# Attiny_MCU_Module.net
KiCad netlist of a schematic drawn in EAGLE
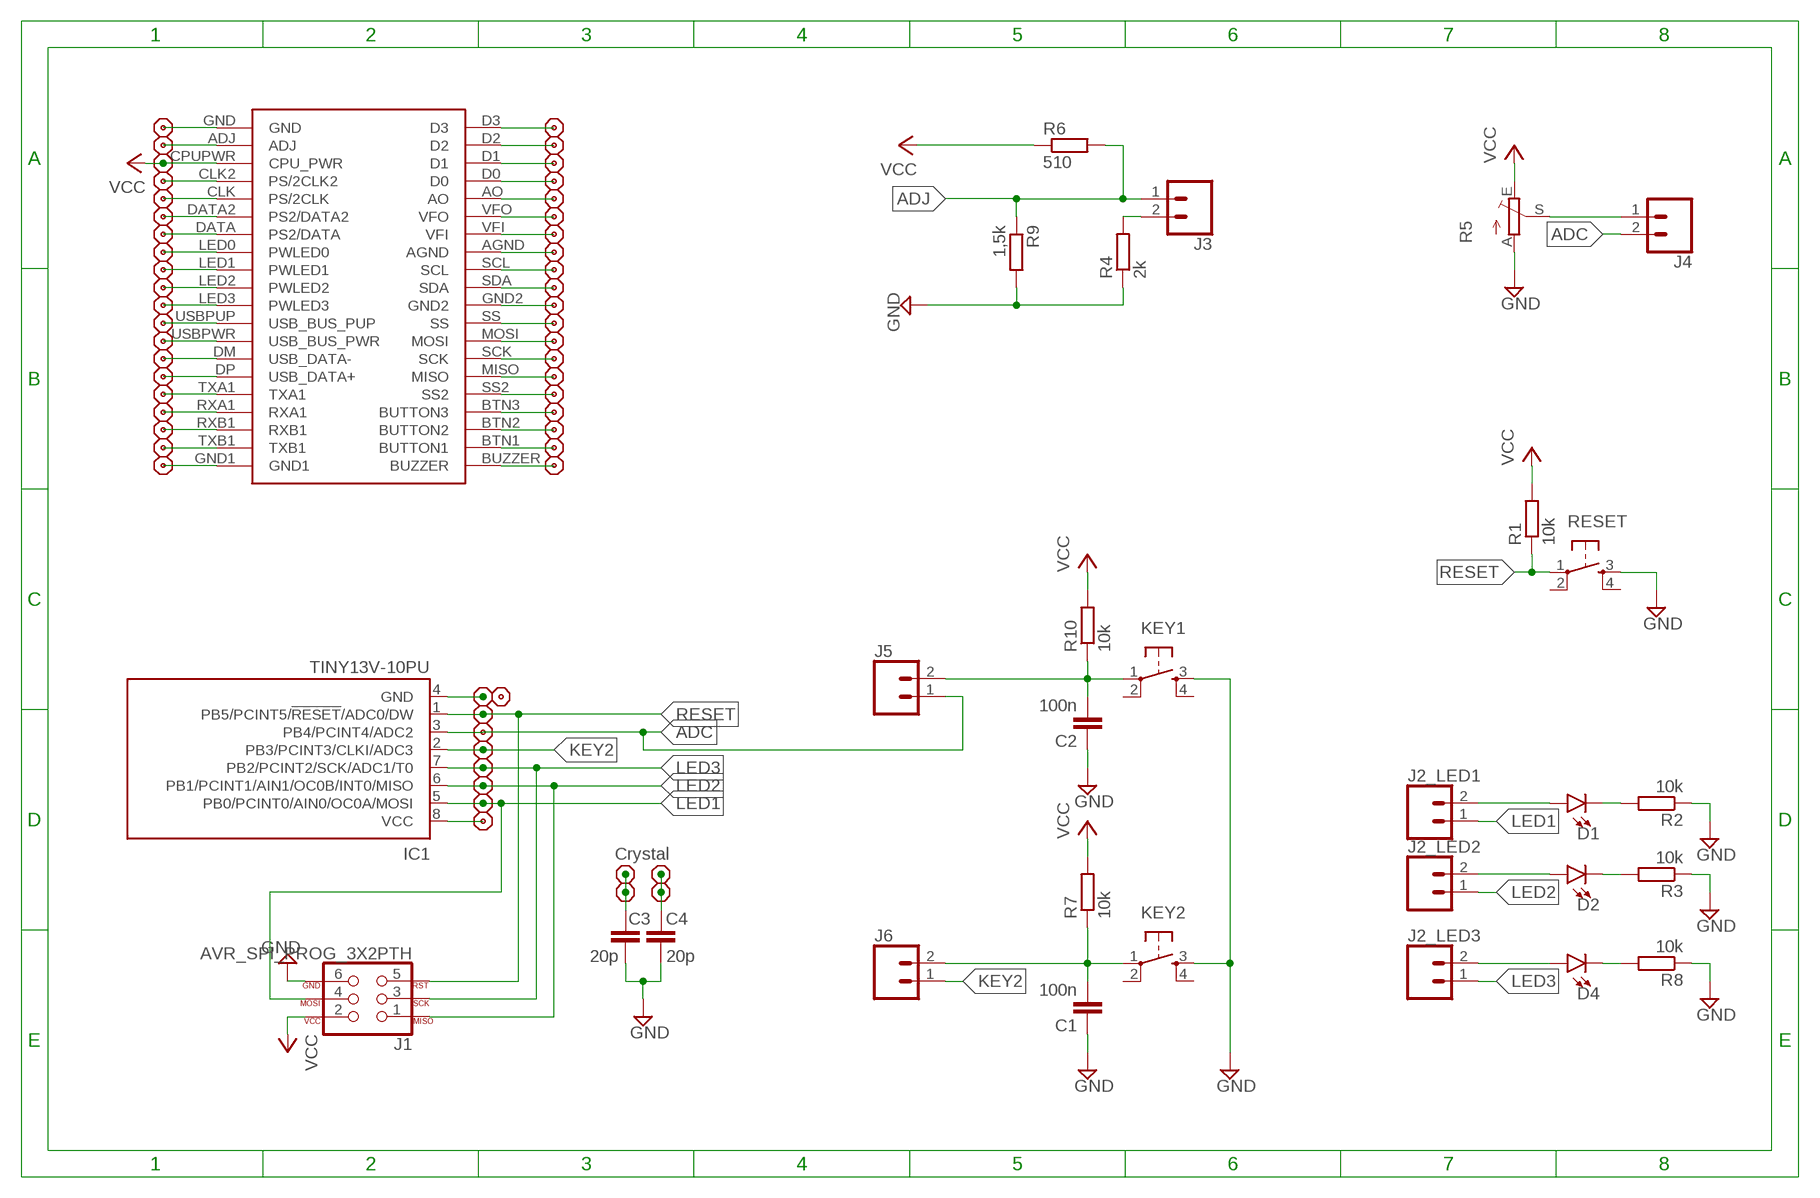
[diagram p0: schematic, sheet 1]

(export (version "E")
  (design (tool "Eeschema 10.0.6"))
  (components
    (comp (ref "C1")
      (value "100n")
      (footprint "eagle-import:C1206")
      (libsource (lib "eagle-import") (part "C-EUC1206"))
    )
    (comp (ref "C2")
      (value "100n")
      (footprint "eagle-import:C1206")
      (libsource (lib "eagle-import") (part "C-EUC1206"))
    )
    (comp (ref "C3")
      (value "20p")
      (footprint "eagle-import:C1206")
      (libsource (lib "eagle-import") (part "C-EUC1206"))
    )
    (comp (ref "C4")
      (value "20p")
      (footprint "eagle-import:C1206")
      (libsource (lib "eagle-import") (part "C-EUC1206"))
    )
    (comp (ref "D1")
      (value "LED1206")
      (footprint "eagle-import:LED-1206")
      (libsource (lib "eagle-import") (part "LED1206"))
    )
    (comp (ref "D2")
      (value "LED1206")
      (footprint "eagle-import:LED-1206")
      (libsource (lib "eagle-import") (part "LED1206"))
    )
    (comp (ref "D4")
      (value "LED1206")
      (footprint "eagle-import:LED-1206")
      (libsource (lib "eagle-import") (part "LED1206"))
    )
    (comp (ref "IC1")
      (value "TINY13V-10PU")
      (footprint "eagle-import:DIL08")
      (fields (field (name "MPN") "ATTINY13V-10PU"))
      (libsource (lib "eagle-import") (part "TINY13PUV-10"))
    )
    (comp (ref "J1")
      (value "AVR_SPI_PROG_3X2PTH")
      (footprint "eagle-import:2X3")
      (libsource (lib "eagle-import") (part "AVR_SPI_PROG_3X2PTH"))
    )
    (comp (ref "J2_LED1")
      (value "CONN_02")
      (footprint "eagle-import:1X02")
      (libsource (lib "eagle-import") (part "CONN_02"))
    )
    (comp (ref "J2_LED2")
      (value "CONN_02")
      (footprint "eagle-import:1X02")
      (libsource (lib "eagle-import") (part "CONN_02"))
    )
    (comp (ref "J2_LED3")
      (value "CONN_02")
      (footprint "eagle-import:1X02")
      (libsource (lib "eagle-import") (part "CONN_02"))
    )
    (comp (ref "J3")
      (value "CONN_02")
      (footprint "eagle-import:1X02")
      (libsource (lib "eagle-import") (part "CONN_02"))
    )
    (comp (ref "J4")
      (value "CONN_02")
      (footprint "eagle-import:1X02")
      (libsource (lib "eagle-import") (part "CONN_02"))
    )
    (comp (ref "J5")
      (value "CONN_02")
      (footprint "eagle-import:1X02")
      (libsource (lib "eagle-import") (part "CONN_02"))
    )
    (comp (ref "J6")
      (value "CONN_02")
      (footprint "eagle-import:1X02")
      (libsource (lib "eagle-import") (part "CONN_02"))
    )
    (comp (ref "JP1")
      (value "PINHD-1X1PIN")
      (footprint "eagle-import:1X01")
      (libsource (lib "eagle-import") (part "PINHD-1X1PIN"))
    )
    (comp (ref "JP2")
      (value "PINHD-1X1PIN")
      (footprint "eagle-import:1X01")
      (libsource (lib "eagle-import") (part "PINHD-1X1PIN"))
    )
    (comp (ref "JP3")
      (value "PINHD-1X1PIN")
      (footprint "eagle-import:1X01")
      (libsource (lib "eagle-import") (part "PINHD-1X1PIN"))
    )
    (comp (ref "JP4")
      (value "PINHD-1X1PIN")
      (footprint "eagle-import:1X01")
      (libsource (lib "eagle-import") (part "PINHD-1X1PIN"))
    )
    (comp (ref "JP5")
      (value "PINHD-1X1PIN")
      (footprint "eagle-import:1X01")
      (libsource (lib "eagle-import") (part "PINHD-1X1PIN"))
    )
    (comp (ref "JP6")
      (value "PINHD-1X1PIN")
      (footprint "eagle-import:1X01")
      (libsource (lib "eagle-import") (part "PINHD-1X1PIN"))
    )
    (comp (ref "JP7")
      (value "PINHD-1X1PIN")
      (footprint "eagle-import:1X01")
      (libsource (lib "eagle-import") (part "PINHD-1X1PIN"))
    )
    (comp (ref "JP8")
      (value "PINHD-1X1PIN")
      (footprint "eagle-import:1X01")
      (libsource (lib "eagle-import") (part "PINHD-1X1PIN"))
    )
    (comp (ref "JP9")
      (value "PINHD-1X1PIN")
      (footprint "eagle-import:1X01")
      (libsource (lib "eagle-import") (part "PINHD-1X1PIN"))
    )
    (comp (ref "JP10")
      (value "PINHD-1X1PIN")
      (footprint "eagle-import:1X01")
      (libsource (lib "eagle-import") (part "PINHD-1X1PIN"))
    )
    (comp (ref "JP11")
      (value "PINHD-1X1PIN")
      (footprint "eagle-import:1X01")
      (libsource (lib "eagle-import") (part "PINHD-1X1PIN"))
    )
    (comp (ref "JP12")
      (value "PINHD-1X1PIN")
      (footprint "eagle-import:1X01")
      (libsource (lib "eagle-import") (part "PINHD-1X1PIN"))
    )
    (comp (ref "JP13")
      (value "PINHD-1X1PIN")
      (footprint "eagle-import:1X01")
      (libsource (lib "eagle-import") (part "PINHD-1X1PIN"))
    )
    (comp (ref "KEY1")
      (value "TAC_SWITCHPTH")
      (footprint "eagle-import:TACTILE-PTH")
      (libsource (lib "eagle-import") (part "TAC_SWITCHPTH"))
    )
    (comp (ref "KEY2")
      (value "TAC_SWITCHPTH")
      (footprint "eagle-import:TACTILE-PTH")
      (libsource (lib "eagle-import") (part "TAC_SWITCHPTH"))
    )
    (comp (ref "R1")
      (value "10k")
      (footprint "eagle-import:M1206")
      (libsource (lib "eagle-import") (part "R-EU_M1206"))
    )
    (comp (ref "R2")
      (value "10k")
      (footprint "eagle-import:M1206")
      (libsource (lib "eagle-import") (part "R-EU_M1206"))
    )
    (comp (ref "R3")
      (value "10k")
      (footprint "eagle-import:M1206")
      (libsource (lib "eagle-import") (part "R-EU_M1206"))
    )
    (comp (ref "R4")
      (value "2k")
      (footprint "eagle-import:M1206")
      (libsource (lib "eagle-import") (part "R-EU_M1206"))
    )
    (comp (ref "R5")
      (value "TRIM_EU-B25P")
      (footprint "eagle-import:B25P")
      (libsource (lib "eagle-import") (part "TRIM_EU-B25P"))
    )
    (comp (ref "R6")
      (value "510")
      (footprint "eagle-import:M1206")
      (libsource (lib "eagle-import") (part "R-EU_M1206"))
    )
    (comp (ref "R7")
      (value "10k")
      (footprint "eagle-import:M1206")
      (libsource (lib "eagle-import") (part "R-EU_M1206"))
    )
    (comp (ref "R8")
      (value "10k")
      (footprint "eagle-import:M1206")
      (libsource (lib "eagle-import") (part "R-EU_M1206"))
    )
    (comp (ref "R9")
      (value "1,5k")
      (footprint "eagle-import:M1206")
      (libsource (lib "eagle-import") (part "R-EU_M1206"))
    )
    (comp (ref "R10")
      (value "10k")
      (footprint "eagle-import:M1206")
      (libsource (lib "eagle-import") (part "R-EU_M1206"))
    )
    (comp (ref "RESET")
      (value "TAC_SWITCHPTH")
      (footprint "eagle-import:TACTILE-PTH")
      (libsource (lib "eagle-import") (part "TAC_SWITCHPTH"))
    )
    (comp (ref "U$1")
      (value "CPU_CON")
      (footprint "eagle-import:CPU_SHIELD")
      (libsource (lib "eagle-import") (part "CPU_CON"))
    )
    (comp (ref "U$2")
      (value "PINHD1X20")
      (footprint "eagle-import:PINHD1X20")
      (libsource (lib "eagle-import") (part "PINHD1X20"))
    )
    (comp (ref "U$3")
      (value "PINHD1X20")
      (footprint "eagle-import:PINHD1X20")
      (libsource (lib "eagle-import") (part "PINHD1X20"))
    )
  )
  (nets
    (net (code "1") (name "ADC") (class "Default")
      (node (ref "IC1") (pin "3") (pinfunction "PB4/PCINT4/ADC2_3") (pintype "bidirectional"))
      (node (ref "J4") (pin "2") (pinfunction "2_2") (pintype "passive"))
      (node (ref "J5") (pin "1") (pinfunction "1_1") (pintype "passive"))
      (node (ref "JP3") (pin "1") (pinfunction "1_1") (pintype "passive"))
    )
    (net (code "2") (name "ADJ") (class "Default")
      (node (ref "J3") (pin "1") (pinfunction "1_1") (pintype "passive"))
      (node (ref "R6") (pin "2") (pinfunction "2_2") (pintype "passive"))
      (node (ref "R9") (pin "1") (pinfunction "1_1") (pintype "passive"))
      (node (ref "U$1") (pin "ADJ") (pinfunction "ADJ_ADJ") (pintype "bidirectional"))
      (node (ref "U$3") (pin "19") (pinfunction "19_19") (pintype "passive"))
    )
    (net (code "3") (name "GND") (class "Default")
      (node (ref "C1") (pin "1") (pinfunction "1_1") (pintype "passive"))
      (node (ref "C2") (pin "1") (pinfunction "1_1") (pintype "passive"))
      (node (ref "C3") (pin "1") (pinfunction "1_1") (pintype "passive"))
      (node (ref "C4") (pin "1") (pinfunction "1_1") (pintype "passive"))
      (node (ref "IC1") (pin "4") (pinfunction "GND_4") (pintype "power_in"))
      (node (ref "J1") (pin "6") (pinfunction "6_6") (pintype "passive"))
      (node (ref "JP1") (pin "1") (pinfunction "1_1") (pintype "passive"))
      (node (ref "KEY1") (pin "3") (pinfunction "3_3") (pintype "passive"))
      (node (ref "KEY2") (pin "3") (pinfunction "3_3") (pintype "passive"))
      (node (ref "R2") (pin "1") (pinfunction "1_1") (pintype "passive"))
      (node (ref "R3") (pin "1") (pinfunction "1_1") (pintype "passive"))
      (node (ref "R4") (pin "1") (pinfunction "1_1") (pintype "passive"))
      (node (ref "R5") (pin "A") (pinfunction "A_A") (pintype "passive"))
      (node (ref "R8") (pin "1") (pinfunction "1_1") (pintype "passive"))
      (node (ref "R9") (pin "2") (pinfunction "2_2") (pintype "passive"))
      (node (ref "RESET") (pin "3") (pinfunction "3_3") (pintype "passive"))
      (node (ref "U$1") (pin "GND") (pinfunction "GND_GND") (pintype "bidirectional"))
      (node (ref "U$1") (pin "GND1") (pinfunction "GND1_GND1") (pintype "bidirectional"))
      (node (ref "U$1") (pin "GND2") (pinfunction "GND2_GND2") (pintype "bidirectional"))
      (node (ref "U$2") (pin "10") (pinfunction "10_10") (pintype "passive"))
      (node (ref "U$3") (pin "1") (pinfunction "1_1") (pintype "passive"))
      (node (ref "U$3") (pin "20") (pinfunction "20_20") (pintype "passive"))
    )
    (net (code "4") (name "KEY2") (class "Default")
      (node (ref "IC1") (pin "2") (pinfunction "PB3/PCINT3/CLKI/ADC3_2") (pintype "bidirectional"))
      (node (ref "J6") (pin "1") (pinfunction "1_1") (pintype "passive"))
      (node (ref "JP4") (pin "1") (pinfunction "1_1") (pintype "passive"))
    )
    (net (code "5") (name "LED1") (class "Default")
      (node (ref "IC1") (pin "5") (pinfunction "PB0/PCINT0/AIN0/OC0A/MOSI_5") (pintype "bidirectional"))
      (node (ref "J1") (pin "4") (pinfunction "4_4") (pintype "passive"))
      (node (ref "J2_LED1") (pin "1") (pinfunction "1_1") (pintype "passive"))
      (node (ref "JP7") (pin "1") (pinfunction "1_1") (pintype "passive"))
    )
    (net (code "6") (name "LED2") (class "Default")
      (node (ref "IC1") (pin "6") (pinfunction "PB1/PCINT1/AIN1/OC0B/INT0/MISO_6") (pintype "bidirectional"))
      (node (ref "J1") (pin "1") (pinfunction "1_1") (pintype "passive"))
      (node (ref "J2_LED2") (pin "1") (pinfunction "1_1") (pintype "passive"))
      (node (ref "JP6") (pin "1") (pinfunction "1_1") (pintype "passive"))
    )
    (net (code "7") (name "LED3") (class "Default")
      (node (ref "IC1") (pin "7") (pinfunction "PB2/PCINT2/SCK/ADC1/T0_7") (pintype "bidirectional"))
      (node (ref "J1") (pin "3") (pinfunction "3_3") (pintype "passive"))
      (node (ref "J2_LED3") (pin "1") (pinfunction "1_1") (pintype "passive"))
      (node (ref "JP5") (pin "1") (pinfunction "1_1") (pintype "passive"))
    )
    (net (code "8") (name "Net-(C1-Pad2)") (class "Default")
      (node (ref "C1") (pin "2") (pinfunction "2_2") (pintype "passive"))
      (node (ref "J6") (pin "2") (pinfunction "2_2") (pintype "passive"))
      (node (ref "KEY2") (pin "1") (pinfunction "1_1") (pintype "passive"))
      (node (ref "R7") (pin "1") (pinfunction "1_1") (pintype "passive"))
    )
    (net (code "9") (name "Net-(C2-Pad2)") (class "Default")
      (node (ref "C2") (pin "2") (pinfunction "2_2") (pintype "passive"))
      (node (ref "J5") (pin "2") (pinfunction "2_2") (pintype "passive"))
      (node (ref "KEY1") (pin "1") (pinfunction "1_1") (pintype "passive"))
      (node (ref "R10") (pin "1") (pinfunction "1_1") (pintype "passive"))
    )
    (net (code "10") (name "Net-(C3-Pad2)") (class "Default")
      (node (ref "C3") (pin "2") (pinfunction "2_2") (pintype "passive"))
      (node (ref "JP10") (pin "1") (pinfunction "1_1") (pintype "passive"))
      (node (ref "JP11") (pin "1") (pinfunction "1_1") (pintype "passive"))
    )
    (net (code "11") (name "Net-(C4-Pad2)") (class "Default")
      (node (ref "C4") (pin "2") (pinfunction "2_2") (pintype "passive"))
      (node (ref "JP12") (pin "1") (pinfunction "1_1") (pintype "passive"))
      (node (ref "JP9") (pin "1") (pinfunction "1_1") (pintype "passive"))
    )
    (net (code "12") (name "Net-(D1-PadA)") (class "Default")
      (node (ref "D1") (pin "A") (pinfunction "A_A") (pintype "passive"))
      (node (ref "J2_LED1") (pin "2") (pinfunction "2_2") (pintype "passive"))
    )
    (net (code "13") (name "Net-(D1-PadC)") (class "Default")
      (node (ref "D1") (pin "C") (pinfunction "C_C") (pintype "passive"))
      (node (ref "R2") (pin "2") (pinfunction "2_2") (pintype "passive"))
    )
    (net (code "14") (name "Net-(D2-PadA)") (class "Default")
      (node (ref "D2") (pin "A") (pinfunction "A_A") (pintype "passive"))
      (node (ref "J2_LED2") (pin "2") (pinfunction "2_2") (pintype "passive"))
    )
    (net (code "15") (name "Net-(D2-PadC)") (class "Default")
      (node (ref "D2") (pin "C") (pinfunction "C_C") (pintype "passive"))
      (node (ref "R3") (pin "2") (pinfunction "2_2") (pintype "passive"))
    )
    (net (code "16") (name "Net-(D4-PadA)") (class "Default")
      (node (ref "D4") (pin "A") (pinfunction "A_A") (pintype "passive"))
      (node (ref "J2_LED3") (pin "2") (pinfunction "2_2") (pintype "passive"))
    )
    (net (code "17") (name "Net-(D4-PadC)") (class "Default")
      (node (ref "D4") (pin "C") (pinfunction "C_C") (pintype "passive"))
      (node (ref "R8") (pin "2") (pinfunction "2_2") (pintype "passive"))
    )
    (net (code "18") (name "Net-(J3-Pad2)") (class "Default")
      (node (ref "J3") (pin "2") (pinfunction "2_2") (pintype "passive"))
      (node (ref "R4") (pin "2") (pinfunction "2_2") (pintype "passive"))
    )
    (net (code "19") (name "Net-(J4-Pad1)") (class "Default")
      (node (ref "J4") (pin "1") (pinfunction "1_1") (pintype "passive"))
      (node (ref "R5") (pin "S") (pinfunction "S_S") (pintype "passive"))
    )
    (net (code "20") (name "Net-(U$1-BUTTON1)") (class "Default")
      (node (ref "U$1") (pin "BTN1") (pinfunction "BUTTON1_BTN1") (pintype "bidirectional"))
      (node (ref "U$2") (pin "2") (pinfunction "2_2") (pintype "passive"))
    )
    (net (code "21") (name "Net-(U$1-BUTTON2)") (class "Default")
      (node (ref "U$1") (pin "BTN2") (pinfunction "BUTTON2_BTN2") (pintype "bidirectional"))
      (node (ref "U$2") (pin "3") (pinfunction "3_3") (pintype "passive"))
    )
    (net (code "22") (name "Net-(U$1-BUTTON3)") (class "Default")
      (node (ref "U$1") (pin "BTN3") (pinfunction "BUTTON3_BTN3") (pintype "bidirectional"))
      (node (ref "U$2") (pin "4") (pinfunction "4_4") (pintype "passive"))
    )
    (net (code "23") (name "Net-(U$1-PS2{slash}DATA)") (class "Default")
      (node (ref "U$1") (pin "DATA") (pinfunction "PS2/DATA_DATA") (pintype "bidirectional"))
      (node (ref "U$3") (pin "14") (pinfunction "14_14") (pintype "passive"))
    )
    (net (code "24") (name "Net-(U$1-PS2{slash}DATA2)") (class "Default")
      (node (ref "U$1") (pin "DATA2") (pinfunction "PS2/DATA2_DATA2") (pintype "bidirectional"))
      (node (ref "U$3") (pin "15") (pinfunction "15_15") (pintype "passive"))
    )
    (net (code "25") (name "Net-(U$1-PS{slash}2CLK)") (class "Default")
      (node (ref "U$1") (pin "CLK") (pinfunction "PS/2CLK_CLK") (pintype "bidirectional"))
      (node (ref "U$3") (pin "16") (pinfunction "16_16") (pintype "passive"))
    )
    (net (code "26") (name "Net-(U$1-PS{slash}2CLK2)") (class "Default")
      (node (ref "U$1") (pin "CLK2") (pinfunction "PS/2CLK2_CLK2") (pintype "bidirectional"))
      (node (ref "U$3") (pin "17") (pinfunction "17_17") (pintype "passive"))
    )
    (net (code "27") (name "Net-(U$1-PWLED0)") (class "Default")
      (node (ref "U$1") (pin "LED0") (pinfunction "PWLED0_LED0") (pintype "bidirectional"))
      (node (ref "U$3") (pin "13") (pinfunction "13_13") (pintype "passive"))
    )
    (net (code "28") (name "Net-(U$1-PWLED1)") (class "Default")
      (node (ref "U$1") (pin "LED1") (pinfunction "PWLED1_LED1") (pintype "bidirectional"))
      (node (ref "U$3") (pin "12") (pinfunction "12_12") (pintype "passive"))
    )
    (net (code "29") (name "Net-(U$1-PWLED2)") (class "Default")
      (node (ref "U$1") (pin "LED2") (pinfunction "PWLED2_LED2") (pintype "bidirectional"))
      (node (ref "U$3") (pin "11") (pinfunction "11_11") (pintype "passive"))
    )
    (net (code "30") (name "Net-(U$1-PWLED3)") (class "Default")
      (node (ref "U$1") (pin "LED3") (pinfunction "PWLED3_LED3") (pintype "bidirectional"))
      (node (ref "U$3") (pin "10") (pinfunction "10_10") (pintype "passive"))
    )
    (net (code "31") (name "Net-(U$1-PadAGND)") (class "Default")
      (node (ref "U$1") (pin "AGND") (pinfunction "AGND_AGND") (pintype "bidirectional"))
      (node (ref "U$2") (pin "13") (pinfunction "13_13") (pintype "passive"))
    )
    (net (code "32") (name "Net-(U$1-PadAO)") (class "Default")
      (node (ref "U$1") (pin "AO") (pinfunction "AO_AO") (pintype "bidirectional"))
      (node (ref "U$2") (pin "16") (pinfunction "16_16") (pintype "passive"))
    )
    (net (code "33") (name "Net-(U$1-PadBUZZER)") (class "Default")
      (node (ref "U$1") (pin "BUZZER") (pinfunction "BUZZER_BUZZER") (pintype "bidirectional"))
      (node (ref "U$2") (pin "1") (pinfunction "1_1") (pintype "passive"))
    )
    (net (code "34") (name "Net-(U$1-PadD0)") (class "Default")
      (node (ref "U$1") (pin "D0") (pinfunction "D0_D0") (pintype "bidirectional"))
      (node (ref "U$2") (pin "17") (pinfunction "17_17") (pintype "passive"))
    )
    (net (code "35") (name "Net-(U$1-PadD1)") (class "Default")
      (node (ref "U$1") (pin "D1") (pinfunction "D1_D1") (pintype "bidirectional"))
      (node (ref "U$2") (pin "18") (pinfunction "18_18") (pintype "passive"))
    )
    (net (code "36") (name "Net-(U$1-PadD2)") (class "Default")
      (node (ref "U$1") (pin "D2") (pinfunction "D2_D2") (pintype "bidirectional"))
      (node (ref "U$2") (pin "19") (pinfunction "19_19") (pintype "passive"))
    )
    (net (code "37") (name "Net-(U$1-PadD3)") (class "Default")
      (node (ref "U$1") (pin "D3") (pinfunction "D3_D3") (pintype "bidirectional"))
      (node (ref "U$2") (pin "20") (pinfunction "20_20") (pintype "passive"))
    )
    (net (code "38") (name "Net-(U$1-PadMISO)") (class "Default")
      (node (ref "U$1") (pin "MISO") (pinfunction "MISO_MISO") (pintype "bidirectional"))
      (node (ref "U$2") (pin "6") (pinfunction "6_6") (pintype "passive"))
    )
    (net (code "39") (name "Net-(U$1-PadMOSI)") (class "Default")
      (node (ref "U$1") (pin "MOSI") (pinfunction "MOSI_MOSI") (pintype "bidirectional"))
      (node (ref "U$2") (pin "8") (pinfunction "8_8") (pintype "passive"))
    )
    (net (code "40") (name "Net-(U$1-PadRXA1)") (class "Default")
      (node (ref "U$1") (pin "RXA1") (pinfunction "RXA1_RXA1") (pintype "bidirectional"))
      (node (ref "U$3") (pin "4") (pinfunction "4_4") (pintype "passive"))
    )
    (net (code "41") (name "Net-(U$1-PadRXB1)") (class "Default")
      (node (ref "U$1") (pin "RXB1") (pinfunction "RXB1_RXB1") (pintype "bidirectional"))
      (node (ref "U$3") (pin "3") (pinfunction "3_3") (pintype "passive"))
    )
    (net (code "42") (name "Net-(U$1-PadSCK)") (class "Default")
      (node (ref "U$1") (pin "SCK") (pinfunction "SCK_SCK") (pintype "bidirectional"))
      (node (ref "U$2") (pin "7") (pinfunction "7_7") (pintype "passive"))
    )
    (net (code "43") (name "Net-(U$1-PadSCL)") (class "Default")
      (node (ref "U$1") (pin "SCL") (pinfunction "SCL_SCL") (pintype "bidirectional"))
      (node (ref "U$2") (pin "12") (pinfunction "12_12") (pintype "passive"))
    )
    (net (code "44") (name "Net-(U$1-PadSDA)") (class "Default")
      (node (ref "U$1") (pin "SDA") (pinfunction "SDA_SDA") (pintype "bidirectional"))
      (node (ref "U$2") (pin "11") (pinfunction "11_11") (pintype "passive"))
    )
    (net (code "45") (name "Net-(U$1-PadSS)") (class "Default")
      (node (ref "U$1") (pin "SS") (pinfunction "SS_SS") (pintype "bidirectional"))
      (node (ref "U$2") (pin "9") (pinfunction "9_9") (pintype "passive"))
    )
    (net (code "46") (name "Net-(U$1-PadSS2)") (class "Default")
      (node (ref "U$1") (pin "SS2") (pinfunction "SS2_SS2") (pintype "bidirectional"))
      (node (ref "U$2") (pin "5") (pinfunction "5_5") (pintype "passive"))
    )
    (net (code "47") (name "Net-(U$1-PadTXA1)") (class "Default")
      (node (ref "U$1") (pin "TXA1") (pinfunction "TXA1_TXA1") (pintype "bidirectional"))
      (node (ref "U$3") (pin "5") (pinfunction "5_5") (pintype "passive"))
    )
    (net (code "48") (name "Net-(U$1-PadTXB1)") (class "Default")
      (node (ref "U$1") (pin "TXB1") (pinfunction "TXB1_TXB1") (pintype "bidirectional"))
      (node (ref "U$3") (pin "2") (pinfunction "2_2") (pintype "passive"))
    )
    (net (code "49") (name "Net-(U$1-PadVFI)") (class "Default")
      (node (ref "U$1") (pin "VFI") (pinfunction "VFI_VFI") (pintype "bidirectional"))
      (node (ref "U$2") (pin "14") (pinfunction "14_14") (pintype "passive"))
    )
    (net (code "50") (name "Net-(U$1-PadVFO)") (class "Default")
      (node (ref "U$1") (pin "VFO") (pinfunction "VFO_VFO") (pintype "bidirectional"))
      (node (ref "U$2") (pin "15") (pinfunction "15_15") (pintype "passive"))
    )
    (net (code "51") (name "Net-(U$1-USB_BUS_PUP)") (class "Default")
      (node (ref "U$1") (pin "USBPUP") (pinfunction "USB_BUS_PUP_USBPUP") (pintype "bidirectional"))
      (node (ref "U$3") (pin "9") (pinfunction "9_9") (pintype "passive"))
    )
    (net (code "52") (name "Net-(U$1-USB_BUS_PWR)") (class "Default")
      (node (ref "U$1") (pin "USBPWR") (pinfunction "USB_BUS_PWR_USBPWR") (pintype "bidirectional"))
      (node (ref "U$3") (pin "8") (pinfunction "8_8") (pintype "passive"))
    )
    (net (code "53") (name "Net-(U$1-USB_DATA+)") (class "Default")
      (node (ref "U$1") (pin "DP") (pinfunction "USB_DATA+_DP") (pintype "bidirectional"))
      (node (ref "U$3") (pin "6") (pinfunction "6_6") (pintype "passive"))
    )
    (net (code "54") (name "Net-(U$1-USB_DATA-)") (class "Default")
      (node (ref "U$1") (pin "DM") (pinfunction "USB_DATA-_DM") (pintype "bidirectional"))
      (node (ref "U$3") (pin "7") (pinfunction "7_7") (pintype "passive"))
    )
    (net (code "55") (name "RESET") (class "Default")
      (node (ref "IC1") (pin "1") (pinfunction "PB5/PCINT5/~{RESET}/ADC0/DW_1") (pintype "bidirectional"))
      (node (ref "J1") (pin "5") (pinfunction "5_5") (pintype "passive"))
      (node (ref "JP2") (pin "1") (pinfunction "1_1") (pintype "passive"))
      (node (ref "R1") (pin "1") (pinfunction "1_1") (pintype "passive"))
      (node (ref "RESET") (pin "1") (pinfunction "1_1") (pintype "passive"))
    )
    (net (code "56") (name "VCC") (class "Default")
      (node (ref "IC1") (pin "8") (pinfunction "VCC_8") (pintype "power_in"))
      (node (ref "J1") (pin "2") (pinfunction "2_2") (pintype "passive"))
      (node (ref "JP8") (pin "1") (pinfunction "1_1") (pintype "passive"))
      (node (ref "R1") (pin "2") (pinfunction "2_2") (pintype "passive"))
      (node (ref "R10") (pin "2") (pinfunction "2_2") (pintype "passive"))
      (node (ref "R5") (pin "E") (pinfunction "E_E") (pintype "passive"))
      (node (ref "R6") (pin "1") (pinfunction "1_1") (pintype "passive"))
      (node (ref "R7") (pin "2") (pinfunction "2_2") (pintype "passive"))
      (node (ref "U$1") (pin "CPUPWR") (pinfunction "CPU_PWR_CPUPWR") (pintype "bidirectional"))
      (node (ref "U$3") (pin "18") (pinfunction "18_18") (pintype "passive"))
    )
    (net (code "57") (name "unconnected-(JP13-Pad1)") (class "Default")
      (node (ref "JP13") (pin "1") (pinfunction "1_1") (pintype "passive"))
    )
    (net (code "58") (name "unconnected-(KEY1-Pad2)") (class "Default")
      (node (ref "KEY1") (pin "2") (pinfunction "2_2") (pintype "passive"))
    )
    (net (code "59") (name "unconnected-(KEY1-Pad4)") (class "Default")
      (node (ref "KEY1") (pin "4") (pinfunction "4_4") (pintype "passive"))
    )
    (net (code "60") (name "unconnected-(KEY2-Pad2)") (class "Default")
      (node (ref "KEY2") (pin "2") (pinfunction "2_2") (pintype "passive"))
    )
    (net (code "61") (name "unconnected-(KEY2-Pad4)") (class "Default")
      (node (ref "KEY2") (pin "4") (pinfunction "4_4") (pintype "passive"))
    )
    (net (code "62") (name "unconnected-(RESET-Pad2)") (class "Default")
      (node (ref "RESET") (pin "2") (pinfunction "2_2") (pintype "passive"))
    )
    (net (code "63") (name "unconnected-(RESET-Pad4)") (class "Default")
      (node (ref "RESET") (pin "4") (pinfunction "4_4") (pintype "passive"))
    )
  )
)
